# EEZ_AUX_PS_r4B42.net
KiCad netlist of a schematic drawn in EAGLE
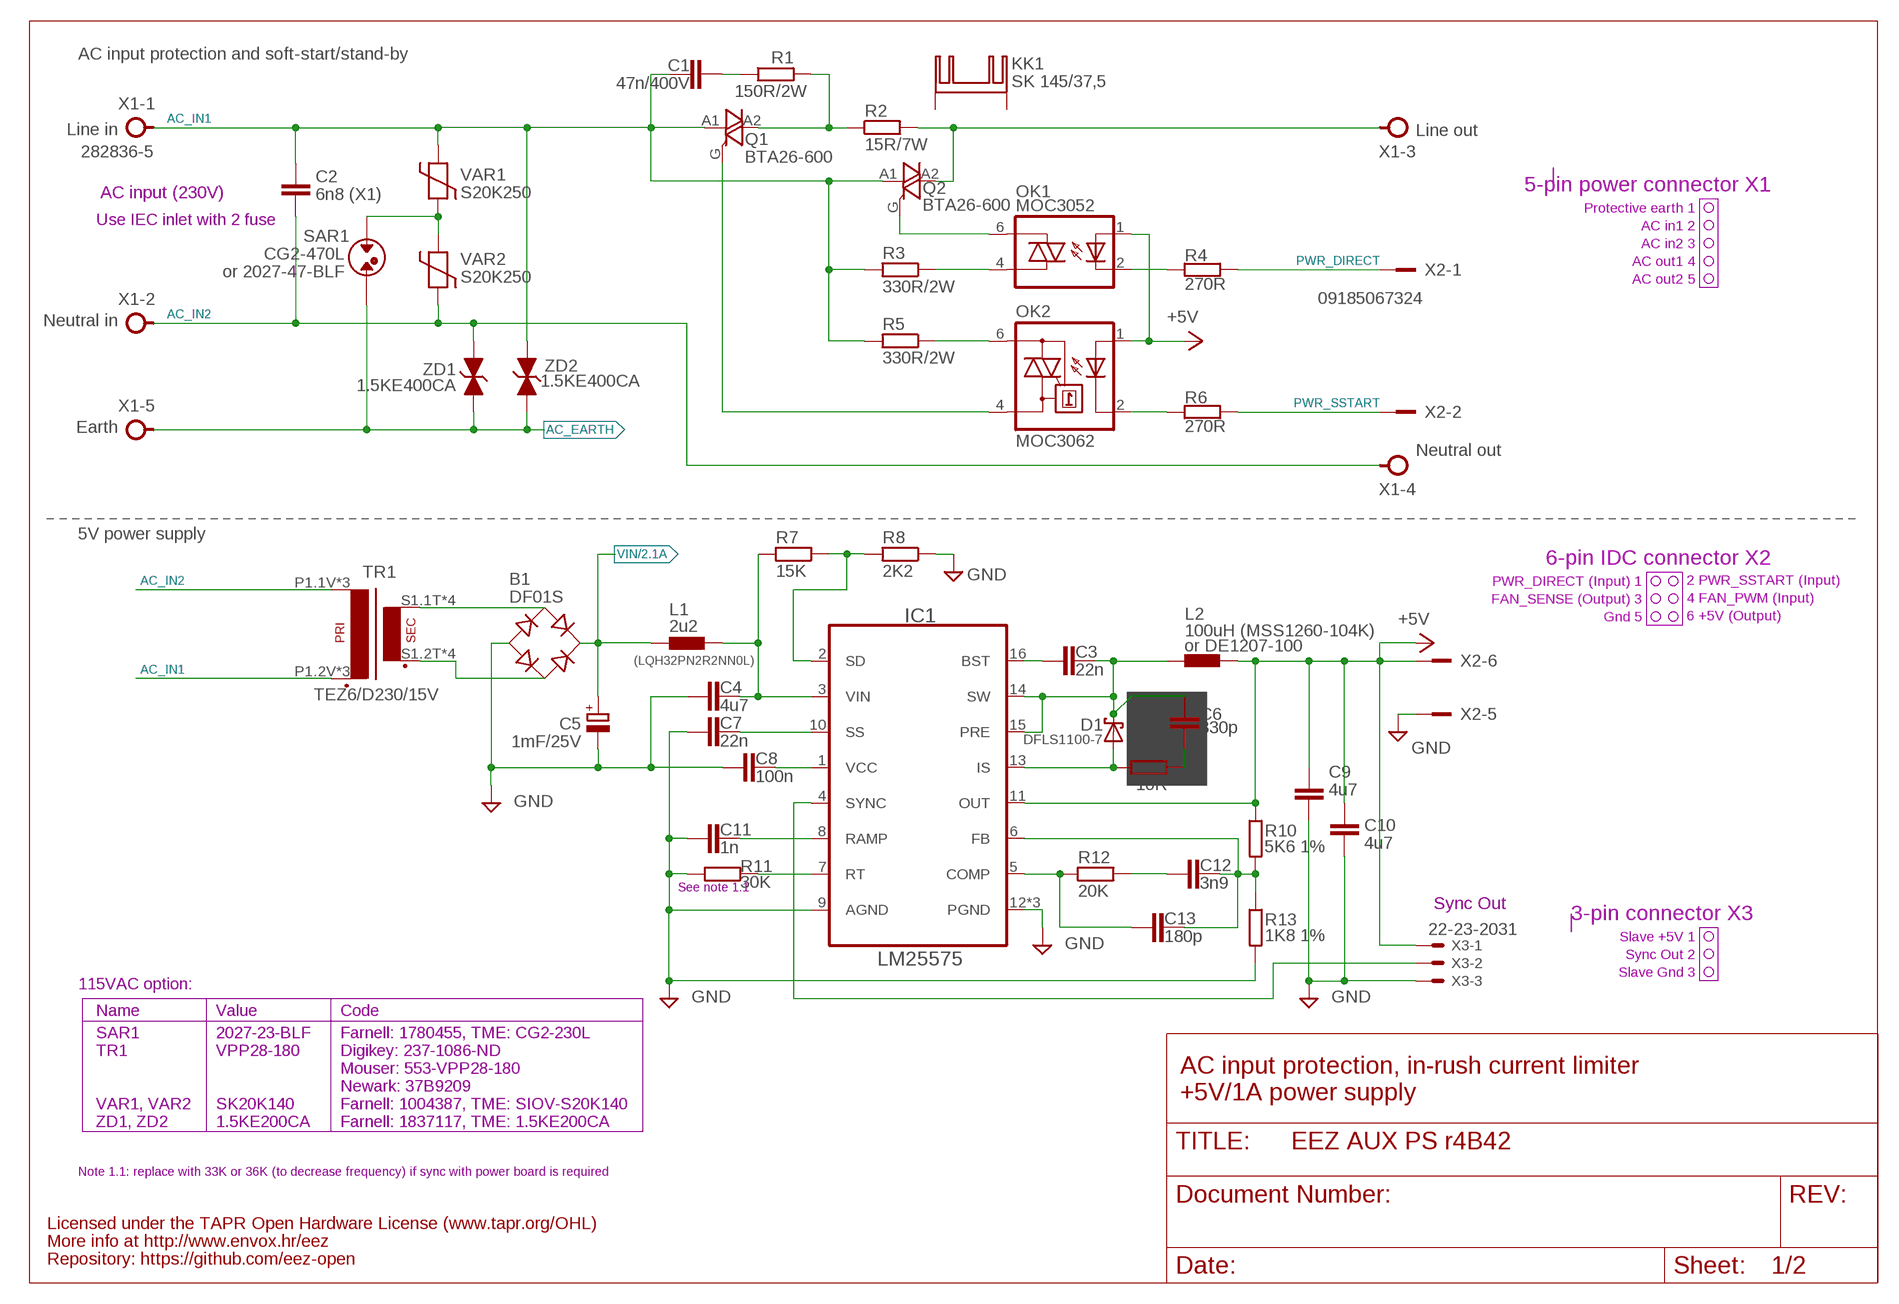
[diagram p0: schematic, sheet 1]
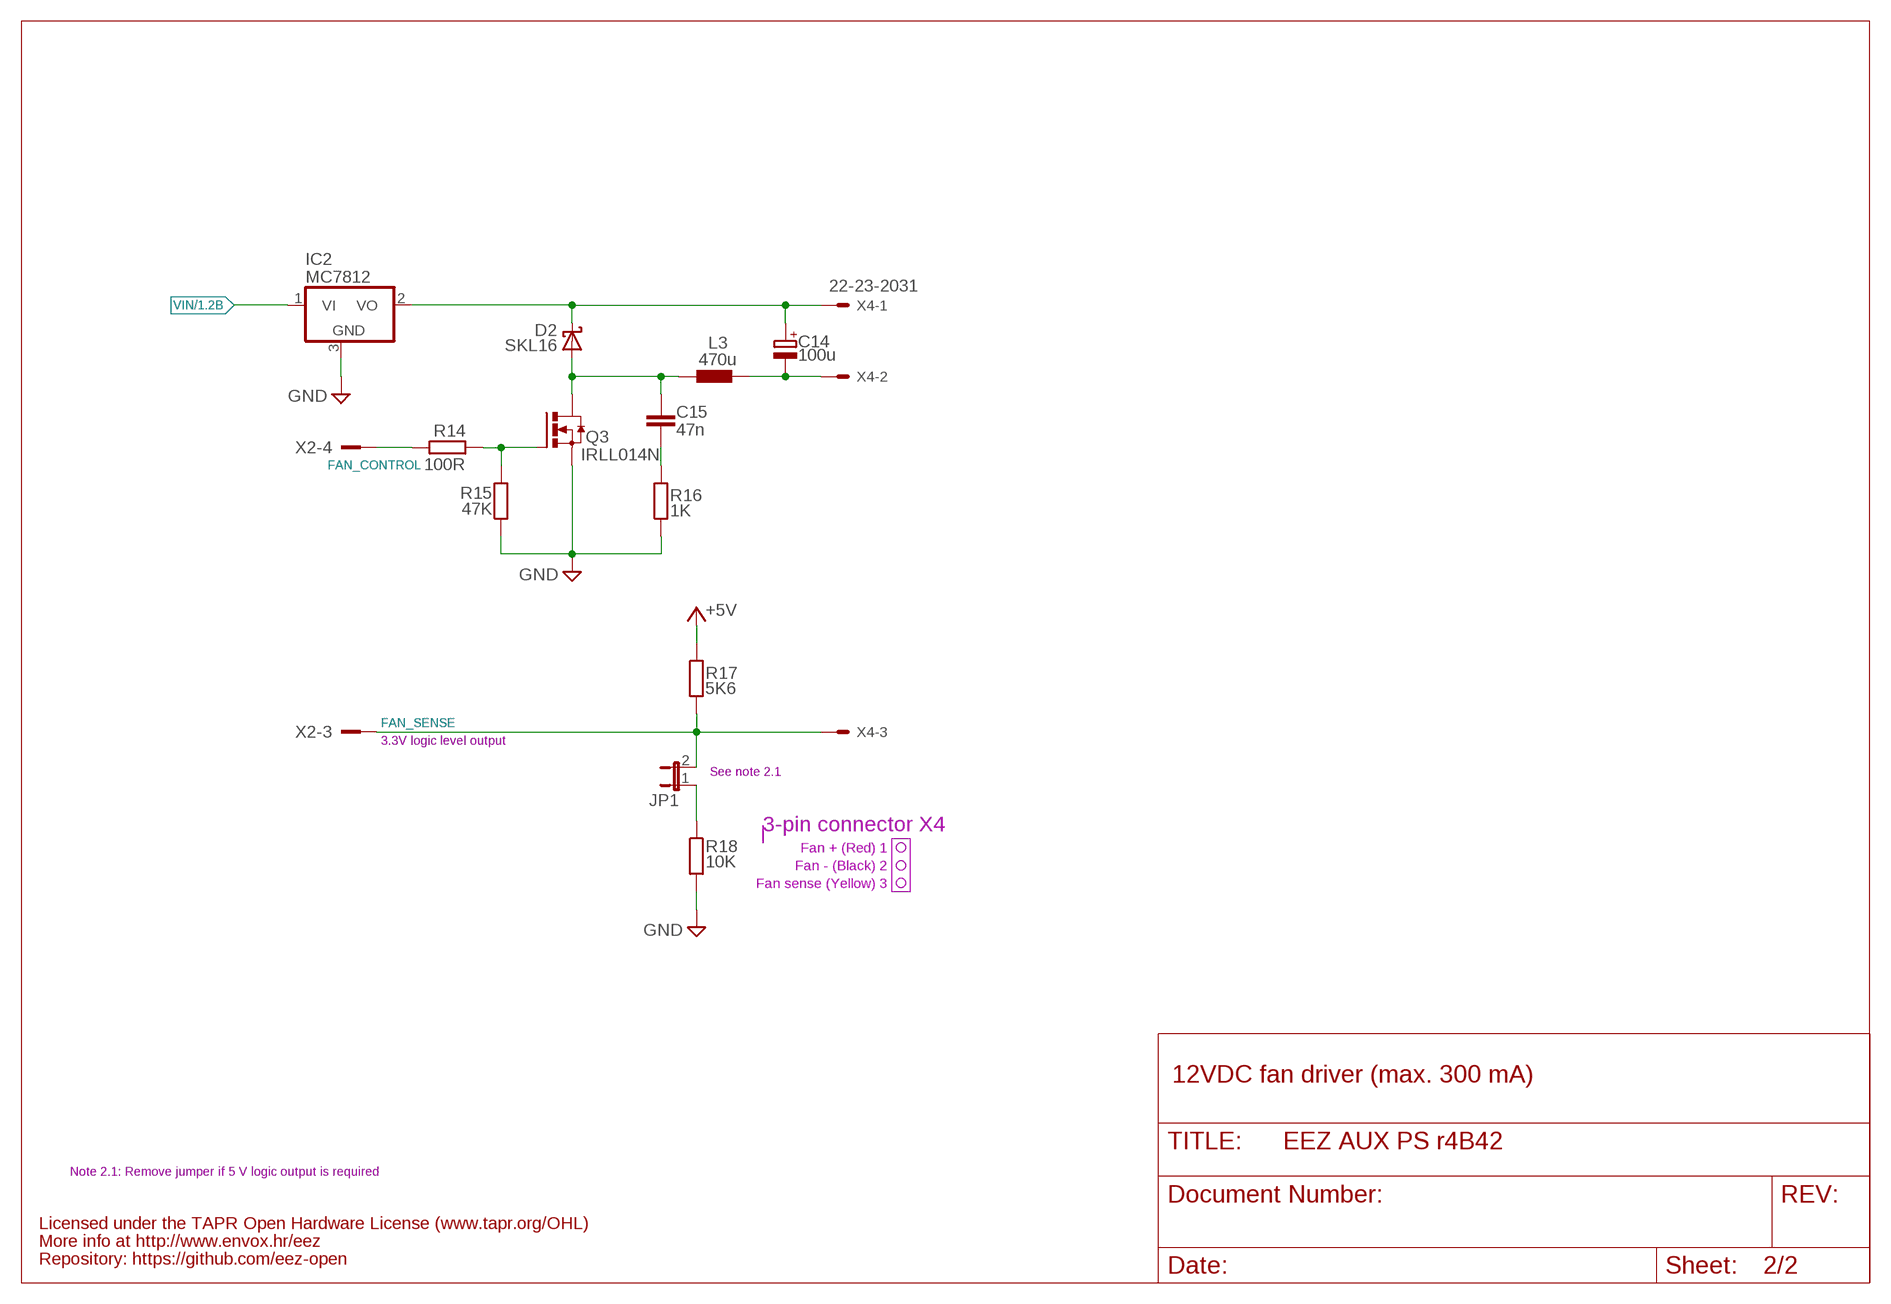
[diagram p1: schematic, sheet 2]

(export (version "E")
  (design (tool "Eeschema 10.0.6"))
  (components
    (comp (ref "C14")
      (value "100u")
      (footprint "eagle-import:CAPAE660X610N")
      (libsource (lib "eagle-import") (part "ECAPPANASONIC_H"))
    )
    (comp (ref "C15")
      (value "47n")
      (footprint "eagle-import:C0805")
      (libsource (lib "eagle-import") (part "C-EUC0805"))
    )
    (comp (ref "D2")
      (value "SKL16")
      (footprint "eagle-import:SOD123")
      (libsource (lib "eagle-import") (part "SCHOTTKYSOD123"))
    )
    (comp (ref "IC2")
      (value "MC7812")
      (footprint "eagle-import:TO252")
      (libsource (lib "eagle-import") (part "MC78XX"))
    )
    (comp (ref "JP1")
      (value "JP1E")
      (footprint "eagle-import:JP1")
      (libsource (lib "eagle-import") (part "JP1E"))
    )
    (comp (ref "L3")
      (value "470u")
      (footprint "eagle-import:DE0704")
      (libsource (lib "eagle-import") (part "DE0704"))
    )
    (comp (ref "Q3")
      (value "IRLL014N")
      (footprint "eagle-import:SOT223")
      (libsource (lib "eagle-import") (part "N-HEXFET-2D_?-SOT232IRLL014N"))
    )
    (comp (ref "R14")
      (value "100R")
      (footprint "eagle-import:R0805")
      (libsource (lib "eagle-import") (part "R-EU_R0805"))
    )
    (comp (ref "R15")
      (value "47K")
      (footprint "eagle-import:R0805")
      (libsource (lib "eagle-import") (part "R-EU_R0805"))
    )
    (comp (ref "R16")
      (value "1K")
      (footprint "eagle-import:R0805")
      (libsource (lib "eagle-import") (part "R-EU_R0805"))
    )
    (comp (ref "R17")
      (value "5K6")
      (footprint "eagle-import:R0805")
      (libsource (lib "eagle-import") (part "R-EU_R0805"))
    )
    (comp (ref "R18")
      (value "10K")
      (footprint "eagle-import:R0805")
      (libsource (lib "eagle-import") (part "R-EU_R0805"))
    )
    (comp (ref "X2")
      (value "09185067324")
      (footprint "eagle-import:IDC-6PIN")
      (libsource (lib "eagle-import") (part "IDC-6PIN"))
    )
    (comp (ref "X4")
      (value "22-23-2031")
      (footprint "eagle-import:22-23-2031")
      (fields (field (name "MF") "MOLEX"))
      (libsource (lib "eagle-import") (part "22-23-2031"))
    )
    (comp (ref "B1")
      (value "DF01S")
      (footprint "eagle-import:DFS")
      (libsource (lib "eagle-import") (part "DFS01"))
    )
    (comp (ref "C1")
      (value "47n/400V")
      (footprint "eagle-import:C075-052X106")
      (libsource (lib "eagle-import") (part "C-EU075-052X106"))
    )
    (comp (ref "C2")
      (value "6n8 (X1)")
      (footprint "eagle-import:C102-064X133")
      (libsource (lib "eagle-import") (part "C-EU102-064X133"))
    )
    (comp (ref "C3")
      (value "22n")
      (footprint "eagle-import:C0805")
      (libsource (lib "eagle-import") (part "C-EUC0805"))
    )
    (comp (ref "C4")
      (value "4u7")
      (footprint "eagle-import:C1210")
      (libsource (lib "eagle-import") (part "C-EUC1210"))
    )
    (comp (ref "C5")
      (value "1mF/25V")
      (footprint "eagle-import:ECAP5_10.5")
      (libsource (lib "eagle-import") (part "ECAP5G_10.5MM"))
    )
    (comp (ref "C6")
      (value "330p")
      (footprint "eagle-import:C0805")
      (libsource (lib "eagle-import") (part "C-EUC0805"))
    )
    (comp (ref "C7")
      (value "22n")
      (footprint "eagle-import:C0805")
      (libsource (lib "eagle-import") (part "C-EUC0805"))
    )
    (comp (ref "C8")
      (value "100n")
      (footprint "eagle-import:C0805")
      (libsource (lib "eagle-import") (part "C-EUC0805"))
    )
    (comp (ref "C9")
      (value "4u7")
      (footprint "eagle-import:C1210")
      (libsource (lib "eagle-import") (part "C-EUC1210"))
    )
    (comp (ref "C10")
      (value "4u7")
      (footprint "eagle-import:C1210")
      (libsource (lib "eagle-import") (part "C-EUC1210"))
    )
    (comp (ref "C11")
      (value "1n")
      (footprint "eagle-import:C0805")
      (libsource (lib "eagle-import") (part "C-EUC0805"))
    )
    (comp (ref "C12")
      (value "3n9")
      (footprint "eagle-import:C0805")
      (libsource (lib "eagle-import") (part "C-EUC0805"))
    )
    (comp (ref "C13")
      (value "180p")
      (footprint "eagle-import:C0805")
      (libsource (lib "eagle-import") (part "C-EUC0805"))
    )
    (comp (ref "D1")
      (value "DFLS1100-7")
      (footprint "eagle-import:SOD123")
      (libsource (lib "eagle-import") (part "SCHOTTKYSOD123"))
    )
    (comp (ref "IC1")
      (value "LM25575")
      (footprint "eagle-import:SOP65P640X110-17N_HOLE")
      (libsource (lib "eagle-import") (part "LM(2)5575"))
    )
    (comp (ref "KK1")
      (value "SK 145/37,5")
      (footprint "eagle-import:SK145")
      (libsource (lib "eagle-import") (part "SK145"))
    )
    (comp (ref "L1")
      (value "2u2")
      (footprint "eagle-import:L1210")
      (libsource (lib "eagle-import") (part "L1210"))
    )
    (comp (ref "L2")
      (value "100uH (MSS1260-104K)")
      (footprint "eagle-import:MSS1278")
      (libsource (lib "eagle-import") (part "COILCRAFT_MSS1278"))
    )
    (comp (ref "OK1")
      (value "MOC3052")
      (footprint "eagle-import:DIL6-SMD")
      (libsource (lib "eagle-import") (part "MOC305X"))
    )
    (comp (ref "OK2")
      (value "MOC3062")
      (footprint "eagle-import:DIL6-SMD")
      (fields
        (field (name "MF") "FAIRCHILD SEMICONDUCTOR")
        (field (name "MPN") "MOC3033S-M")
        (field (name "MF_1") "FAIRCHILD SEMICONDUCTOR")
        (field (name "MPN_1") "MOC3033S-M")
        (field (name "OC_FARNELL") "unknown")
        (field (name "OC_NEWARK") "05C2878")
      )
      (libsource (lib "eagle-import") (part "MOC30S33"))
    )
    (comp (ref "Q1")
      (value "BTA26-600")
      (footprint "eagle-import:TOP3S-1")
      (libsource (lib "eagle-import") (part "BTA26-V"))
    )
    (comp (ref "Q2")
      (value "BTA26-600")
      (footprint "eagle-import:TOP3S-1")
      (libsource (lib "eagle-import") (part "BTA26-V"))
    )
    (comp (ref "R1")
      (value "150R/2W")
      (footprint "eagle-import:R2512")
      (libsource (lib "eagle-import") (part "R-EU_R2512"))
    )
    (comp (ref "R2")
      (value "15R/7W")
      (footprint "eagle-import:R_0913")
      (libsource (lib "eagle-import") (part "R_EU7W"))
    )
    (comp (ref "R3")
      (value "330R/2W")
      (footprint "eagle-import:R2512")
      (libsource (lib "eagle-import") (part "R-EU_R2512"))
    )
    (comp (ref "R4")
      (value "270R")
      (footprint "eagle-import:R0805")
      (libsource (lib "eagle-import") (part "R-EU_R0805"))
    )
    (comp (ref "R5")
      (value "330R/2W")
      (footprint "eagle-import:R2512")
      (libsource (lib "eagle-import") (part "R-EU_R2512"))
    )
    (comp (ref "R6")
      (value "270R")
      (footprint "eagle-import:R0805")
      (libsource (lib "eagle-import") (part "R-EU_R0805"))
    )
    (comp (ref "R7")
      (value "15K")
      (footprint "eagle-import:R0805")
      (libsource (lib "eagle-import") (part "R-EU_R0805"))
    )
    (comp (ref "R8")
      (value "2K2")
      (footprint "eagle-import:R0805")
      (libsource (lib "eagle-import") (part "R-EU_R0805"))
    )
    (comp (ref "R9")
      (value "10R")
      (footprint "eagle-import:R1206")
      (libsource (lib "eagle-import") (part "R-EU_R1206"))
    )
    (comp (ref "R10")
      (value "5K6 1%")
      (footprint "eagle-import:R0805")
      (libsource (lib "eagle-import") (part "R-EU_R0805"))
    )
    (comp (ref "R11")
      (value "30K")
      (footprint "eagle-import:R0805")
      (libsource (lib "eagle-import") (part "R-EU_R0805"))
    )
    (comp (ref "R12")
      (value "20K")
      (footprint "eagle-import:R0805")
      (libsource (lib "eagle-import") (part "R-EU_R0805"))
    )
    (comp (ref "R13")
      (value "1K8 1%")
      (footprint "eagle-import:R0805")
      (libsource (lib "eagle-import") (part "R-EU_R0805"))
    )
    (comp (ref "SAR1")
      (value "CG2-470L")
      (footprint "eagle-import:SAR")
      (libsource (lib "eagle-import") (part "SAR"))
    )
    (comp (ref "TR1")
      (value "TEZ6/D230/15V")
      (footprint "eagle-import:PCB_TRAFO6VA_TEZ+VPP")
      (libsource (lib "eagle-import") (part "PCB_TRAFO6VA_TEZ+VPP"))
    )
    (comp (ref "VAR1")
      (value "S20K250")
      (footprint "eagle-import:VARISTOR")
      (libsource (lib "eagle-import") (part "VARISTOR"))
    )
    (comp (ref "VAR2")
      (value "S20K250")
      (footprint "eagle-import:VARISTOR")
      (libsource (lib "eagle-import") (part "VARISTOR"))
    )
    (comp (ref "X1")
      (value "282836-5")
      (footprint "eagle-import:TBLOCK5.0_5")
      (libsource (lib "eagle-import") (part "TBLOCK5.0_5A"))
    )
    (comp (ref "X3")
      (value "22-23-2031")
      (footprint "eagle-import:22-23-2031")
      (fields (field (name "MF") "MOLEX"))
      (libsource (lib "eagle-import") (part "22-23-2031"))
    )
    (comp (ref "ZD1")
      (value "1.5KE400CA")
      (footprint "eagle-import:DO201-BIDIR")
      (libsource (lib "eagle-import") (part "1.5KE-BIDIR"))
    )
    (comp (ref "ZD2")
      (value "1.5KE400CA")
      (footprint "eagle-import:DO201-BIDIR")
      (libsource (lib "eagle-import") (part "1.5KE-BIDIR"))
    )
  )
  (nets
    (net (code "1") (name "+5V") (class "Default")
      (node (ref "C10") (pin "1") (pinfunction "1_1") (pintype "passive"))
      (node (ref "C9") (pin "1") (pinfunction "1_1") (pintype "passive"))
      (node (ref "IC1") (pin "11") (pinfunction "OUT_11") (pintype "output"))
      (node (ref "L2") (pin "2") (pinfunction "2_2") (pintype "passive"))
      (node (ref "OK1") (pin "1") (pinfunction "A_1") (pintype "passive"))
      (node (ref "OK2") (pin "1") (pinfunction "A_1") (pintype "passive"))
      (node (ref "R10") (pin "1") (pinfunction "1_1") (pintype "passive"))
      (node (ref "R17") (pin "1") (pinfunction "1_1") (pintype "passive"))
      (node (ref "X2") (pin "6") (pinfunction "1_6") (pintype "passive"))
      (node (ref "X3") (pin "1") (pinfunction "S_1") (pintype "passive"))
    )
    (net (code "2") (name "AC_EARTH") (class "Default")
      (node (ref "SAR1") (pin "P$2") (pinfunction "P$2_P$2") (pintype "bidirectional"))
      (node (ref "X1") (pin "5") (pinfunction "1_5") (pintype "bidirectional"))
      (node (ref "ZD1") (pin "C") (pinfunction "1_C") (pintype "passive"))
      (node (ref "ZD2") (pin "C") (pinfunction "1_C") (pintype "passive"))
    )
    (net (code "3") (name "AC_IN1") (class "Default")
      (node (ref "C1") (pin "2") (pinfunction "2_2") (pintype "passive"))
      (node (ref "C2") (pin "1") (pinfunction "1_1") (pintype "passive"))
      (node (ref "Q1") (pin "A1") (pinfunction "A1_A1") (pintype "passive"))
      (node (ref "Q2") (pin "A1") (pinfunction "A1_A1") (pintype "passive"))
      (node (ref "R3") (pin "2") (pinfunction "2_2") (pintype "passive"))
      (node (ref "R5") (pin "2") (pinfunction "2_2") (pintype "passive"))
      (node (ref "TR1") (pin "P1.2V") (pinfunction "P2_P1.2V") (pintype "passive"))
      (node (ref "TR1") (pin "P2.2V") (pinfunction "P2_P2.2V") (pintype "passive"))
      (node (ref "TR1") (pin "P2_TEZ") (pinfunction "P2_P2_TEZ") (pintype "passive"))
      (node (ref "VAR1") (pin "P$2") (pinfunction "P$2_P$2") (pintype "bidirectional"))
      (node (ref "X1") (pin "1") (pinfunction "1_1") (pintype "bidirectional"))
      (node (ref "ZD2") (pin "A") (pinfunction "2_A") (pintype "passive"))
    )
    (net (code "4") (name "AC_IN2") (class "Default")
      (node (ref "C2") (pin "2") (pinfunction "2_2") (pintype "passive"))
      (node (ref "TR1") (pin "P1.1V") (pinfunction "P1_P1.1V") (pintype "passive"))
      (node (ref "TR1") (pin "P1_TEZ") (pinfunction "P1_P1_TEZ") (pintype "passive"))
      (node (ref "TR1") (pin "P2.1V") (pinfunction "P1_P2.1V") (pintype "passive"))
      (node (ref "VAR2") (pin "P$1") (pinfunction "P$1_P$1") (pintype "bidirectional"))
      (node (ref "X1") (pin "2") (pinfunction "1_2") (pintype "bidirectional"))
      (node (ref "X1") (pin "4") (pinfunction "1_4") (pintype "bidirectional"))
      (node (ref "ZD1") (pin "A") (pinfunction "2_A") (pintype "passive"))
    )
    (net (code "5") (name "FAN_CONTROL") (class "Default")
      (node (ref "R14") (pin "2") (pinfunction "2_2") (pintype "passive"))
      (node (ref "X2") (pin "4") (pinfunction "1_4") (pintype "passive"))
    )
    (net (code "6") (name "FAN_SENSE") (class "Default")
      (node (ref "JP1") (pin "2") (pinfunction "2_2") (pintype "passive"))
      (node (ref "R17") (pin "2") (pinfunction "2_2") (pintype "passive"))
      (node (ref "X2") (pin "3") (pinfunction "1_3") (pintype "passive"))
      (node (ref "X4") (pin "3") (pinfunction "S_3") (pintype "passive"))
    )
    (net (code "7") (name "GND") (class "Default")
      (node (ref "B1") (pin "-") (pinfunction "-_-") (pintype "passive"))
      (node (ref "C10") (pin "2") (pinfunction "2_2") (pintype "passive"))
      (node (ref "C11") (pin "1") (pinfunction "1_1") (pintype "passive"))
      (node (ref "C4") (pin "2") (pinfunction "2_2") (pintype "passive"))
      (node (ref "C5") (pin "-") (pinfunction "-_-") (pintype "passive"))
      (node (ref "C7") (pin "2") (pinfunction "2_2") (pintype "passive"))
      (node (ref "C8") (pin "1") (pinfunction "1_1") (pintype "passive"))
      (node (ref "C9") (pin "2") (pinfunction "2_2") (pintype "passive"))
      (node (ref "IC1") (pin "12") (pinfunction "PGND_12") (pintype "passive"))
      (node (ref "IC1") (pin "9") (pinfunction "AGND_9") (pintype "passive"))
      (node (ref "IC1") (pin "TP") (pinfunction "PGND_TP") (pintype "passive"))
      (node (ref "IC1") (pin "TP2") (pinfunction "PGND_TP2") (pintype "passive"))
      (node (ref "IC2") (pin "3") (pinfunction "GND_3") (pintype "passive"))
      (node (ref "Q3") (pin "3") (pinfunction "S_3") (pintype "passive"))
      (node (ref "R11") (pin "2") (pinfunction "2_2") (pintype "passive"))
      (node (ref "R13") (pin "2") (pinfunction "2_2") (pintype "passive"))
      (node (ref "R15") (pin "1") (pinfunction "1_1") (pintype "passive"))
      (node (ref "R16") (pin "1") (pinfunction "1_1") (pintype "passive"))
      (node (ref "R18") (pin "2") (pinfunction "2_2") (pintype "passive"))
      (node (ref "R8") (pin "1") (pinfunction "1_1") (pintype "passive"))
      (node (ref "X2") (pin "5") (pinfunction "1_5") (pintype "passive"))
      (node (ref "X3") (pin "3") (pinfunction "S_3") (pintype "passive"))
    )
    (net (code "8") (name "Net-(B1-PadAC1)") (class "Default")
      (node (ref "B1") (pin "AC1") (pinfunction "AC1_AC1") (pintype "passive"))
      (node (ref "TR1") (pin "S1.1T") (pinfunction "S1_S1.1T") (pintype "passive"))
      (node (ref "TR1") (pin "S1.1V") (pinfunction "S1_S1.1V") (pintype "passive"))
      (node (ref "TR1") (pin "S2.1T") (pinfunction "S1_S2.1T") (pintype "passive"))
      (node (ref "TR1") (pin "S2.1V") (pinfunction "S1_S2.1V") (pintype "passive"))
    )
    (net (code "9") (name "Net-(B1-PadAC2)") (class "Default")
      (node (ref "B1") (pin "AC2") (pinfunction "AC2_AC2") (pintype "passive"))
      (node (ref "TR1") (pin "S1.2T") (pinfunction "S2_S1.2T") (pintype "passive"))
      (node (ref "TR1") (pin "S1.2V") (pinfunction "S2_S1.2V") (pintype "passive"))
      (node (ref "TR1") (pin "S2.2T") (pinfunction "S2_S2.2T") (pintype "passive"))
      (node (ref "TR1") (pin "S2.2V") (pinfunction "S2_S2.2V") (pintype "passive"))
    )
    (net (code "10") (name "Net-(C1-Pad1)") (class "Default")
      (node (ref "C1") (pin "1") (pinfunction "1_1") (pintype "passive"))
      (node (ref "R1") (pin "1") (pinfunction "1_1") (pintype "passive"))
    )
    (net (code "11") (name "Net-(C6-Pad2)") (class "Default")
      (node (ref "C6") (pin "2") (pinfunction "2_2") (pintype "passive"))
      (node (ref "R9") (pin "2") (pinfunction "2_2") (pintype "passive"))
    )
    (net (code "12") (name "Net-(C12-Pad2)") (class "Default")
      (node (ref "C12") (pin "2") (pinfunction "2_2") (pintype "passive"))
      (node (ref "R12") (pin "2") (pinfunction "2_2") (pintype "passive"))
    )
    (net (code "13") (name "Net-(C14-+)") (class "Default")
      (node (ref "C14") (pin "1") (pinfunction "+_1") (pintype "passive"))
      (node (ref "D2") (pin "C") (pinfunction "C_C") (pintype "passive"))
      (node (ref "IC2") (pin "2") (pinfunction "VO_2") (pintype "passive"))
      (node (ref "X4") (pin "1") (pinfunction "S_1") (pintype "passive"))
    )
    (net (code "14") (name "Net-(C14--)") (class "Default")
      (node (ref "C14") (pin "2") (pinfunction "-_2") (pintype "passive"))
      (node (ref "L3") (pin "1") (pinfunction "1_1") (pintype "passive"))
      (node (ref "X4") (pin "2") (pinfunction "S_2") (pintype "passive"))
    )
    (net (code "15") (name "Net-(C15-Pad1)") (class "Default")
      (node (ref "C15") (pin "1") (pinfunction "1_1") (pintype "passive"))
      (node (ref "R16") (pin "2") (pinfunction "2_2") (pintype "passive"))
    )
    (net (code "16") (name "Net-(C15-Pad2)") (class "Default")
      (node (ref "C15") (pin "2") (pinfunction "2_2") (pintype "passive"))
      (node (ref "D2") (pin "A") (pinfunction "A_A") (pintype "passive"))
      (node (ref "L3") (pin "2") (pinfunction "2_2") (pintype "passive"))
      (node (ref "Q3") (pin "2") (pinfunction "D_2") (pintype "passive"))
      (node (ref "Q3") (pin "4") (pinfunction "D_4") (pintype "passive"))
    )
    (net (code "17") (name "Net-(IC1-BST)") (class "Default")
      (node (ref "C3") (pin "2") (pinfunction "2_2") (pintype "passive"))
      (node (ref "IC1") (pin "16") (pinfunction "BST_16") (pintype "input"))
    )
    (net (code "18") (name "Net-(IC1-COMP)") (class "Default")
      (node (ref "C13") (pin "2") (pinfunction "2_2") (pintype "passive"))
      (node (ref "IC1") (pin "5") (pinfunction "COMP_5") (pintype "input"))
      (node (ref "R12") (pin "1") (pinfunction "1_1") (pintype "passive"))
    )
    (net (code "19") (name "Net-(IC1-FB)") (class "Default")
      (node (ref "C12") (pin "1") (pinfunction "1_1") (pintype "passive"))
      (node (ref "C13") (pin "1") (pinfunction "1_1") (pintype "passive"))
      (node (ref "IC1") (pin "6") (pinfunction "FB_6") (pintype "input"))
      (node (ref "R10") (pin "2") (pinfunction "2_2") (pintype "passive"))
      (node (ref "R13") (pin "1") (pinfunction "1_1") (pintype "passive"))
    )
    (net (code "20") (name "Net-(IC1-IS)") (class "Default")
      (node (ref "D1") (pin "A") (pinfunction "A_A") (pintype "passive"))
      (node (ref "IC1") (pin "13") (pinfunction "IS_13") (pintype "input"))
      (node (ref "R9") (pin "1") (pinfunction "1_1") (pintype "passive"))
    )
    (net (code "21") (name "Net-(IC1-PRE)") (class "Default")
      (node (ref "C3") (pin "1") (pinfunction "1_1") (pintype "passive"))
      (node (ref "C6") (pin "1") (pinfunction "1_1") (pintype "passive"))
      (node (ref "D1") (pin "C") (pinfunction "C_C") (pintype "passive"))
      (node (ref "IC1") (pin "14") (pinfunction "SW_14") (pintype "output"))
      (node (ref "IC1") (pin "15") (pinfunction "PRE_15") (pintype "input"))
      (node (ref "L2") (pin "1") (pinfunction "1_1") (pintype "passive"))
    )
    (net (code "22") (name "Net-(IC1-RAMP)") (class "Default")
      (node (ref "C11") (pin "2") (pinfunction "2_2") (pintype "passive"))
      (node (ref "IC1") (pin "8") (pinfunction "RAMP_8") (pintype "input"))
    )
    (net (code "23") (name "Net-(IC1-RT)") (class "Default")
      (node (ref "IC1") (pin "7") (pinfunction "RT_7") (pintype "input"))
      (node (ref "R11") (pin "1") (pinfunction "1_1") (pintype "passive"))
    )
    (net (code "24") (name "Net-(IC1-SD)") (class "Default")
      (node (ref "IC1") (pin "2") (pinfunction "SD_2") (pintype "input"))
      (node (ref "R7") (pin "1") (pinfunction "1_1") (pintype "passive"))
      (node (ref "R8") (pin "2") (pinfunction "2_2") (pintype "passive"))
    )
    (net (code "25") (name "Net-(IC1-SS)") (class "Default")
      (node (ref "C7") (pin "1") (pinfunction "1_1") (pintype "passive"))
      (node (ref "IC1") (pin "10") (pinfunction "SS_10") (pintype "input"))
    )
    (net (code "26") (name "Net-(IC1-SYNC)") (class "Default")
      (node (ref "IC1") (pin "4") (pinfunction "SYNC_4") (pintype "input"))
      (node (ref "X3") (pin "2") (pinfunction "S_2") (pintype "passive"))
    )
    (net (code "27") (name "Net-(IC1-VCC)") (class "Default")
      (node (ref "C8") (pin "2") (pinfunction "2_2") (pintype "passive"))
      (node (ref "IC1") (pin "1") (pinfunction "VCC_1") (pintype "power_in"))
    )
    (net (code "28") (name "Net-(IC1-VIN)") (class "Default")
      (node (ref "C4") (pin "1") (pinfunction "1_1") (pintype "passive"))
      (node (ref "IC1") (pin "3") (pinfunction "VIN_3") (pintype "input"))
      (node (ref "L1") (pin "2") (pinfunction "2_2") (pintype "passive"))
      (node (ref "R7") (pin "2") (pinfunction "2_2") (pintype "passive"))
    )
    (net (code "29") (name "Net-(JP1-Pad1)") (class "Default")
      (node (ref "JP1") (pin "1") (pinfunction "1_1") (pintype "passive"))
      (node (ref "R18") (pin "1") (pinfunction "1_1") (pintype "passive"))
    )
    (net (code "30") (name "Net-(OK1-A1)") (class "Default")
      (node (ref "OK1") (pin "4") (pinfunction "A1_4") (pintype "passive"))
      (node (ref "R3") (pin "1") (pinfunction "1_1") (pintype "passive"))
    )
    (net (code "31") (name "Net-(OK1-A2)") (class "Default")
      (node (ref "OK1") (pin "6") (pinfunction "A2_6") (pintype "passive"))
      (node (ref "Q2") (pin "G") (pinfunction "G_G") (pintype "passive"))
    )
    (net (code "32") (name "Net-(OK1-C)") (class "Default")
      (node (ref "OK1") (pin "2") (pinfunction "C_2") (pintype "passive"))
      (node (ref "R4") (pin "1") (pinfunction "1_1") (pintype "passive"))
    )
    (net (code "33") (name "Net-(OK2-A1)") (class "Default")
      (node (ref "OK2") (pin "4") (pinfunction "A1_4") (pintype "passive"))
      (node (ref "Q1") (pin "G") (pinfunction "G_G") (pintype "passive"))
    )
    (net (code "34") (name "Net-(OK2-A2)") (class "Default")
      (node (ref "OK2") (pin "6") (pinfunction "A2_6") (pintype "passive"))
      (node (ref "R5") (pin "1") (pinfunction "1_1") (pintype "passive"))
    )
    (net (code "35") (name "Net-(OK2-C)") (class "Default")
      (node (ref "OK2") (pin "2") (pinfunction "C_2") (pintype "passive"))
      (node (ref "R6") (pin "1") (pinfunction "1_1") (pintype "passive"))
    )
    (net (code "36") (name "Net-(Q1-PadA2)") (class "Default")
      (node (ref "Q1") (pin "A2") (pinfunction "A2_A2") (pintype "passive"))
      (node (ref "R1") (pin "2") (pinfunction "2_2") (pintype "passive"))
      (node (ref "R2") (pin "1") (pinfunction "1_1") (pintype "passive"))
    )
    (net (code "37") (name "Net-(Q3-G)") (class "Default")
      (node (ref "Q3") (pin "1") (pinfunction "G_1") (pintype "passive"))
      (node (ref "R14") (pin "1") (pinfunction "1_1") (pintype "passive"))
      (node (ref "R15") (pin "2") (pinfunction "2_2") (pintype "passive"))
    )
    (net (code "38") (name "Net-(SAR1-PadP$1)") (class "Default")
      (node (ref "SAR1") (pin "P$1") (pinfunction "P$1_P$1") (pintype "bidirectional"))
      (node (ref "VAR1") (pin "P$1") (pinfunction "P$1_P$1") (pintype "bidirectional"))
      (node (ref "VAR2") (pin "P$2") (pinfunction "P$2_P$2") (pintype "bidirectional"))
    )
    (net (code "39") (name "Net-(X1C-1)") (class "Default")
      (node (ref "Q2") (pin "A2") (pinfunction "A2_A2") (pintype "passive"))
      (node (ref "R2") (pin "2") (pinfunction "2_2") (pintype "passive"))
      (node (ref "X1") (pin "3") (pinfunction "1_3") (pintype "bidirectional"))
    )
    (net (code "40") (name "PWR_DIRECT") (class "Default")
      (node (ref "R4") (pin "2") (pinfunction "2_2") (pintype "passive"))
      (node (ref "X2") (pin "1") (pinfunction "1_1") (pintype "passive"))
    )
    (net (code "41") (name "PWR_SSTART") (class "Default")
      (node (ref "R6") (pin "2") (pinfunction "2_2") (pintype "passive"))
      (node (ref "X2") (pin "2") (pinfunction "1_2") (pintype "passive"))
    )
    (net (code "42") (name "VIN") (class "Default")
      (node (ref "B1") (pin "+") (pinfunction "+_+") (pintype "passive"))
      (node (ref "C5") (pin "+") (pinfunction "+_+") (pintype "passive"))
      (node (ref "IC2") (pin "1") (pinfunction "VI_1") (pintype "input"))
      (node (ref "L1") (pin "1") (pinfunction "1_1") (pintype "passive"))
    )
    (net (code "43") (name "unconnected-(KK1-K-Pad1)") (class "Default")
      (node (ref "KK1") (pin "1") (pinfunction "K_1") (pintype "passive"))
    )
    (net (code "44") (name "unconnected-(KK1-K-Pad2)") (class "Default")
      (node (ref "KK1") (pin "2") (pinfunction "K_2") (pintype "passive"))
    )
  )
)
